# VSCard_v4.net
KiCad netlist of a schematic drawn in EAGLE
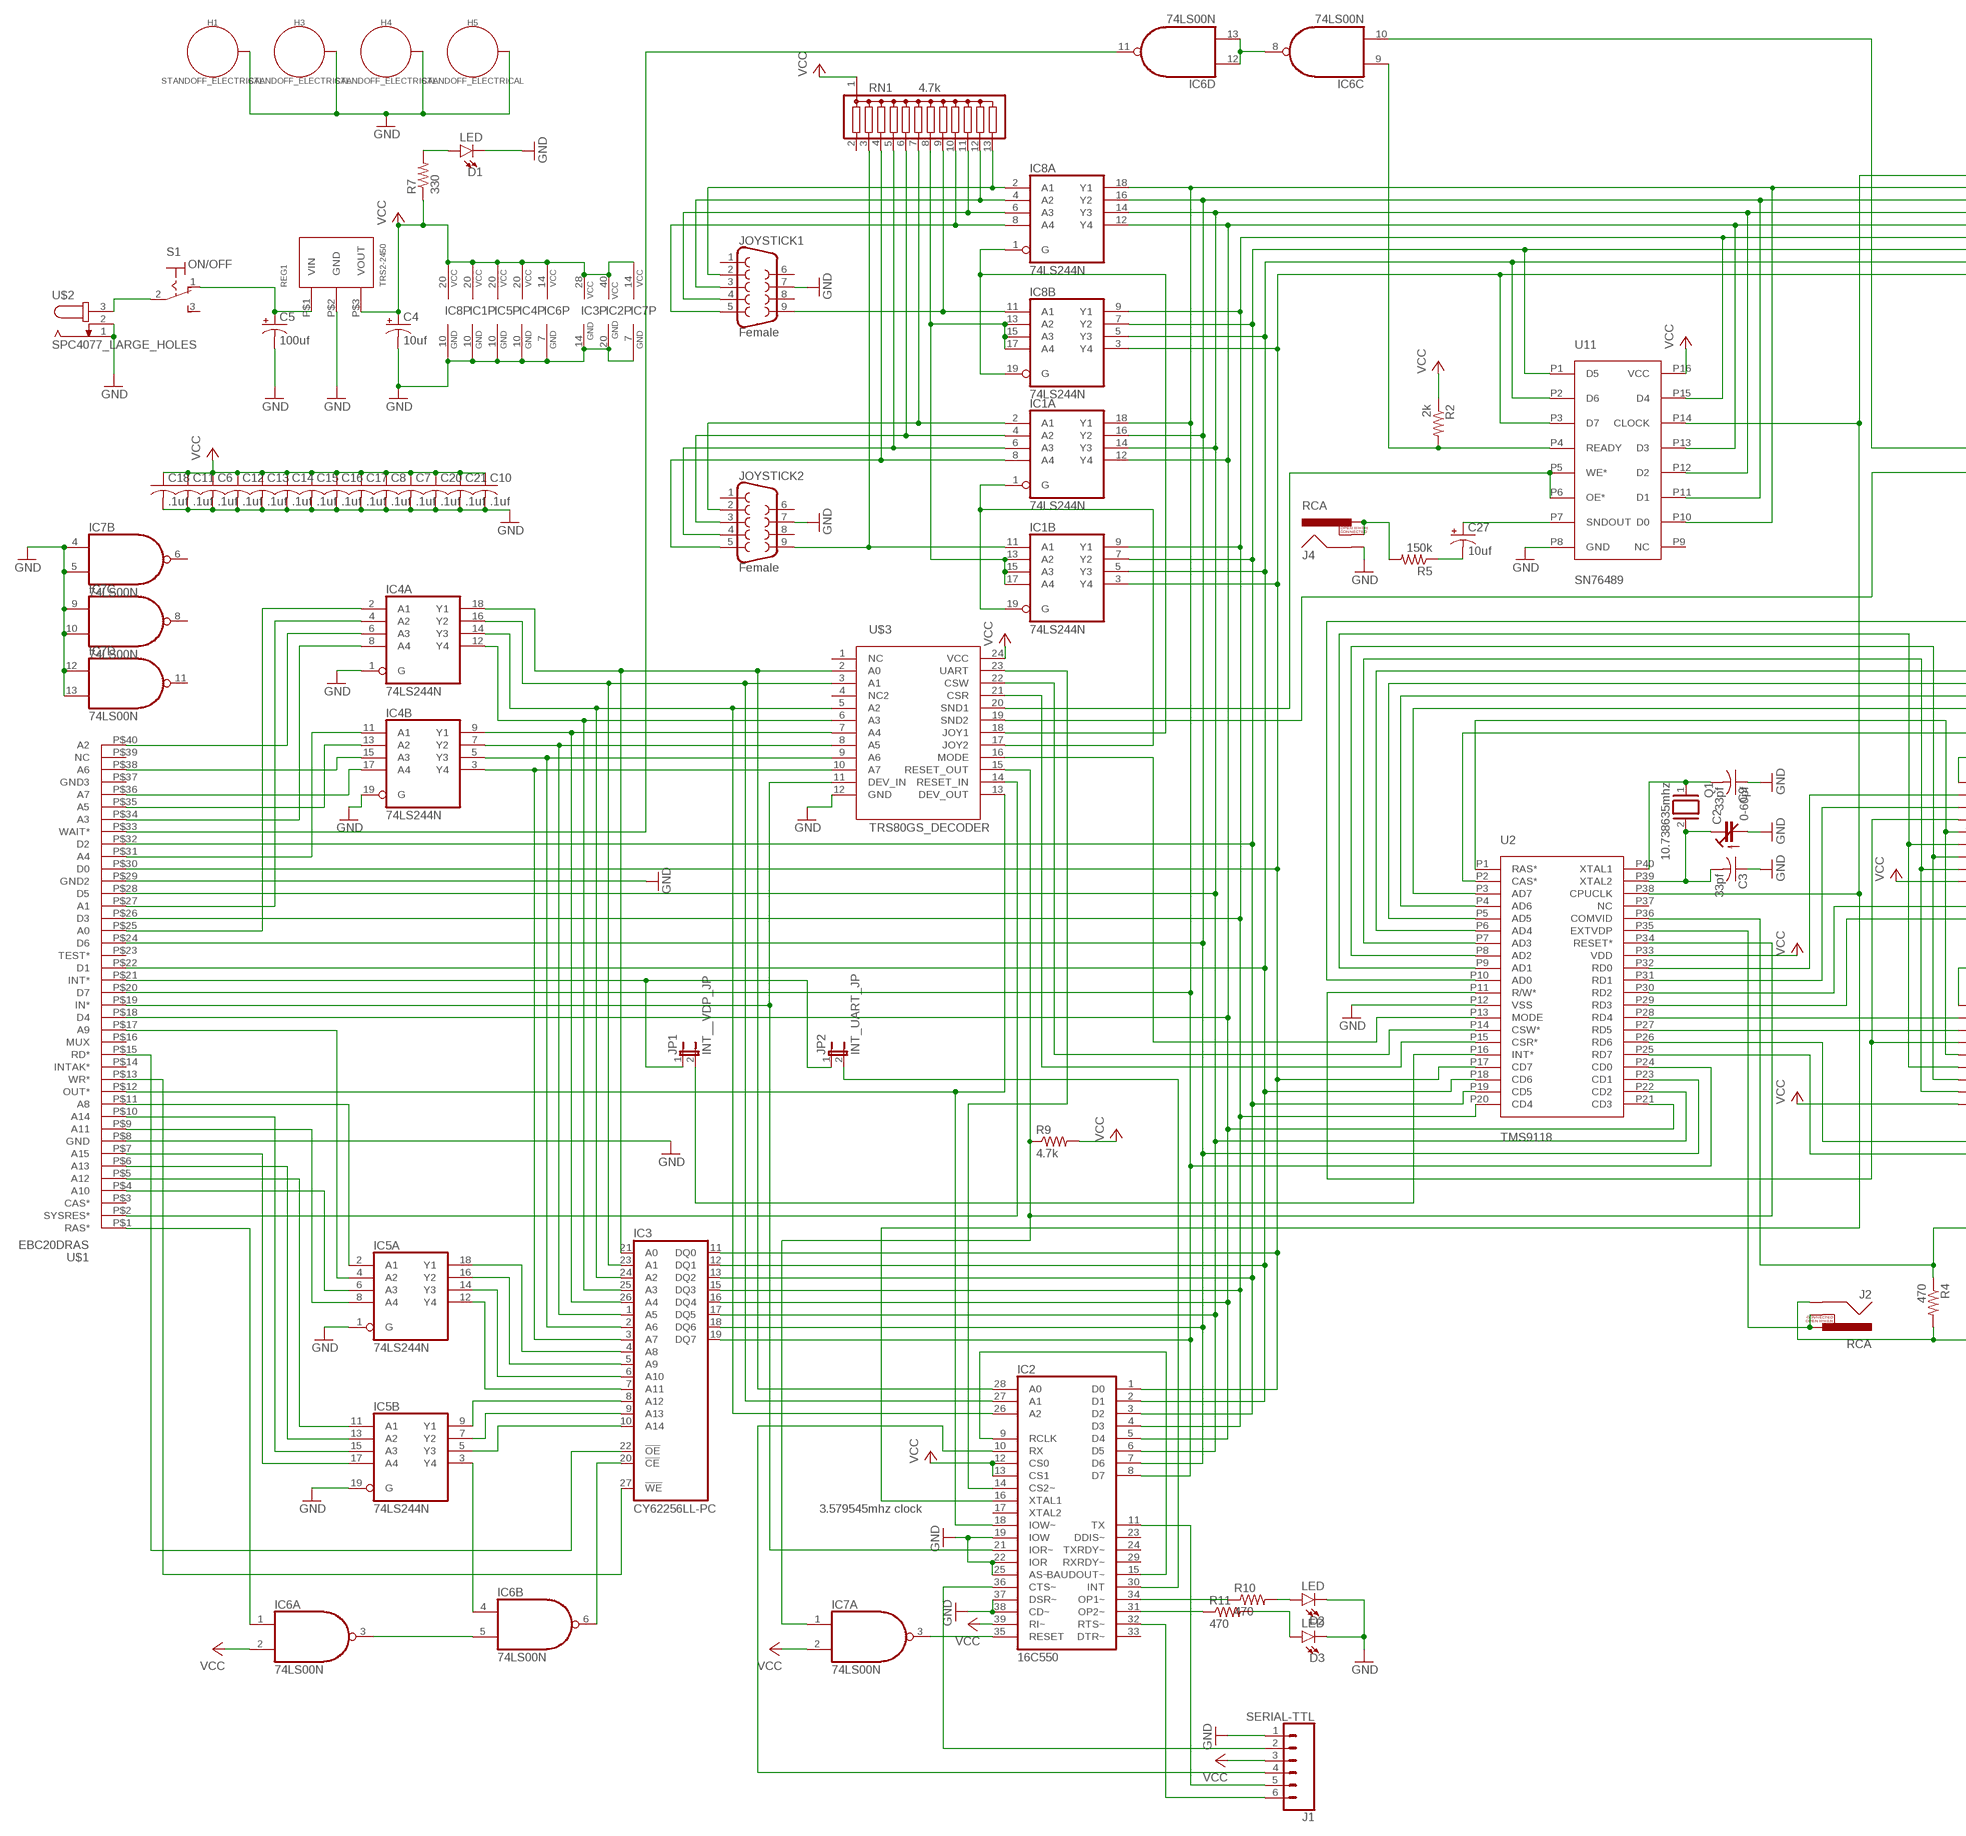
[diagram p0: schematic, sheet 1, part 1 of 2]
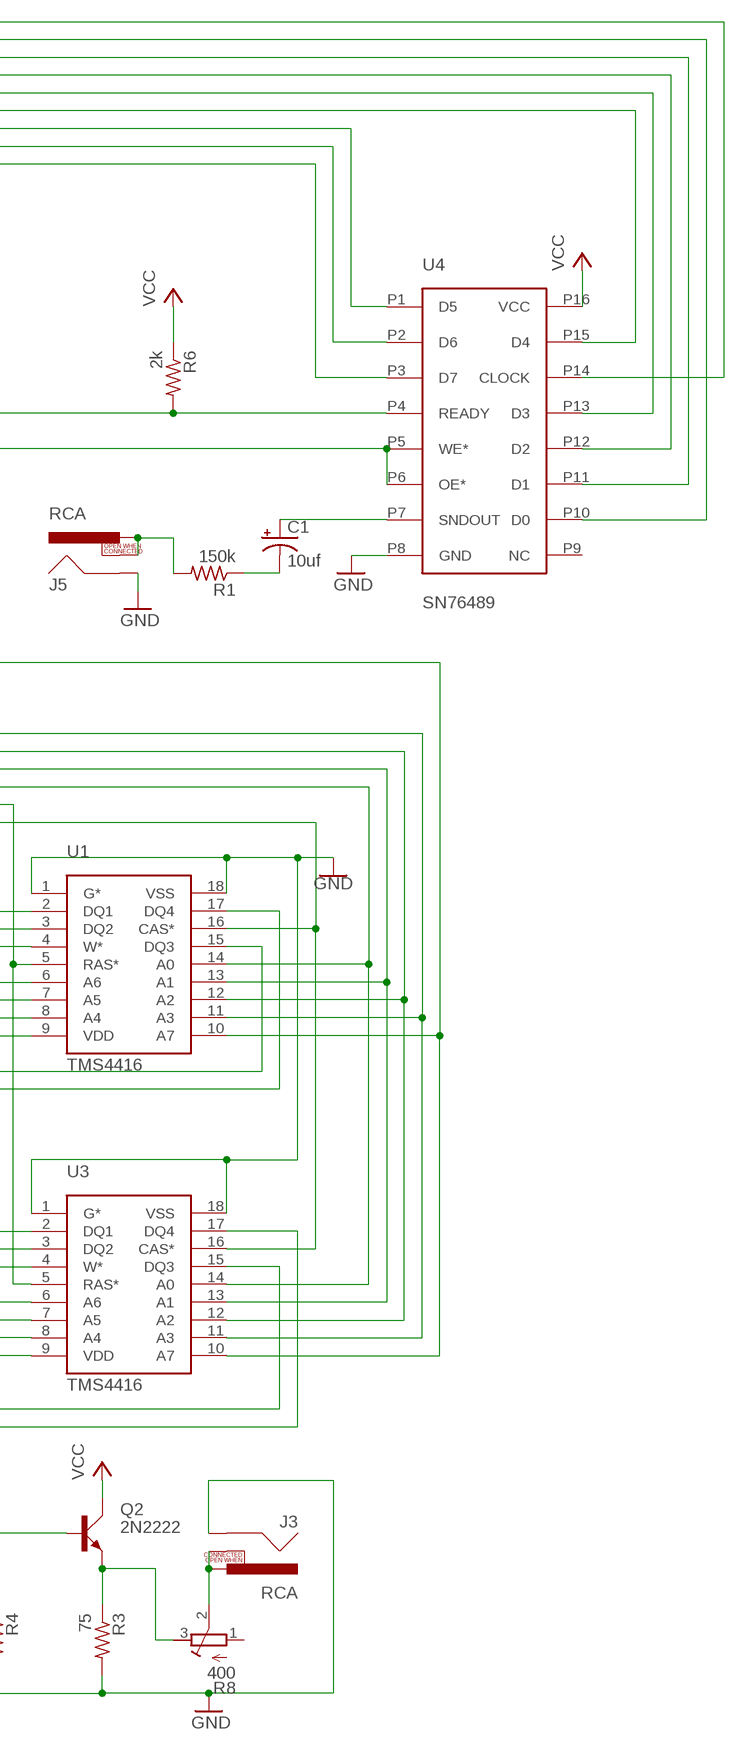
[diagram p1: schematic, sheet 1, part 2 of 2]

(export (version "E")
  (design (tool "Eeschema 10.0.6"))
  (components
    (comp (ref "C1")
      (value "10uf")
      (footprint "eagle-import:E2,5-6")
      (libsource (lib "eagle-import") (part "resistor_348_CPOL-USE2.5-6"))
    )
    (comp (ref "C2")
      (value "0-60pf")
      (footprint "eagle-import:CTRIM3050.504")
      (libsource (lib "eagle-import") (part "C-TRIMM3050.504"))
    )
    (comp (ref "C3")
      (value "33pf")
      (footprint "eagle-import:C050-050X075")
      (libsource (lib "eagle-import") (part "C-US050-050X075"))
    )
    (comp (ref "C4")
      (value "10uf")
      (footprint "eagle-import:E2,5-5")
      (libsource (lib "eagle-import") (part "resistor_348_CPOL-USE2.5-5"))
    )
    (comp (ref "C5")
      (value "100uf")
      (footprint "eagle-import:E3,5-10")
      (libsource (lib "eagle-import") (part "CPOL-USE3.5-10"))
    )
    (comp (ref "C6")
      (value ".1uf")
      (footprint "eagle-import:C025-025X050")
      (libsource (lib "eagle-import") (part "resistor_348_C-US025-025X050"))
    )
    (comp (ref "C7")
      (value ".1uf")
      (footprint "eagle-import:C025-025X050")
      (libsource (lib "eagle-import") (part "resistor_348_C-US025-025X050"))
    )
    (comp (ref "C8")
      (value ".1uf")
      (footprint "eagle-import:C025-025X050")
      (libsource (lib "eagle-import") (part "resistor_348_C-US025-025X050"))
    )
    (comp (ref "C9")
      (value "33pf")
      (footprint "eagle-import:C050-050X075")
      (libsource (lib "eagle-import") (part "C-US050-050X075"))
    )
    (comp (ref "C10")
      (value ".1uf")
      (footprint "eagle-import:C025-025X050")
      (libsource (lib "eagle-import") (part "resistor_348_C-US025-025X050"))
    )
    (comp (ref "C11")
      (value ".1uf")
      (footprint "eagle-import:C025-025X050")
      (libsource (lib "eagle-import") (part "resistor_348_C-US025-025X050"))
    )
    (comp (ref "C12")
      (value ".1uf")
      (footprint "eagle-import:C025-025X050")
      (libsource (lib "eagle-import") (part "resistor_348_C-US025-025X050"))
    )
    (comp (ref "C13")
      (value ".1uf")
      (footprint "eagle-import:C025-025X050")
      (libsource (lib "eagle-import") (part "resistor_348_C-US025-025X050"))
    )
    (comp (ref "C14")
      (value ".1uf")
      (footprint "eagle-import:C025-025X050")
      (libsource (lib "eagle-import") (part "resistor_348_C-US025-025X050"))
    )
    (comp (ref "C15")
      (value ".1uf")
      (footprint "eagle-import:C025-025X050")
      (libsource (lib "eagle-import") (part "resistor_348_C-US025-025X050"))
    )
    (comp (ref "C16")
      (value ".1uf")
      (footprint "eagle-import:C025-025X050")
      (libsource (lib "eagle-import") (part "resistor_348_C-US025-025X050"))
    )
    (comp (ref "C17")
      (value ".1uf")
      (footprint "eagle-import:C025-025X050")
      (libsource (lib "eagle-import") (part "resistor_348_C-US025-025X050"))
    )
    (comp (ref "C18")
      (value ".1uf")
      (footprint "eagle-import:C025-025X050")
      (libsource (lib "eagle-import") (part "resistor_348_C-US025-025X050"))
    )
    (comp (ref "C20")
      (value ".1uf")
      (footprint "eagle-import:C025-025X050")
      (libsource (lib "eagle-import") (part "resistor_348_C-US025-025X050"))
    )
    (comp (ref "C21")
      (value ".1uf")
      (footprint "eagle-import:C025-025X050")
      (libsource (lib "eagle-import") (part "resistor_348_C-US025-025X050"))
    )
    (comp (ref "C27")
      (value "10uf")
      (footprint "eagle-import:E2,5-6")
      (libsource (lib "eagle-import") (part "resistor_348_CPOL-USE2.5-6"))
    )
    (comp (ref "D1")
      (value "LED")
      (footprint "eagle-import:LED_3MM")
      (libsource (lib "eagle-import") (part "LED3MM"))
    )
    (comp (ref "D2")
      (value "LED")
      (footprint "eagle-import:LED_3MM")
      (libsource (lib "eagle-import") (part "LED3MM"))
    )
    (comp (ref "D3")
      (value "LED")
      (footprint "eagle-import:LED_3MM")
      (libsource (lib "eagle-import") (part "LED3MM"))
    )
    (comp (ref "H1")
      (value "STANDOFF_ELECTRICAL")
      (footprint "eagle-import:STANDOFF-ELECTRICAL")
      (libsource (lib "eagle-import") (part "STANDOFF_ELECTRICAL"))
    )
    (comp (ref "H3")
      (value "STANDOFF_ELECTRICAL")
      (footprint "eagle-import:STANDOFF-ELECTRICAL")
      (libsource (lib "eagle-import") (part "STANDOFF_ELECTRICAL"))
    )
    (comp (ref "H4")
      (value "STANDOFF_ELECTRICAL")
      (footprint "eagle-import:STANDOFF-ELECTRICAL")
      (libsource (lib "eagle-import") (part "STANDOFF_ELECTRICAL"))
    )
    (comp (ref "H5")
      (value "STANDOFF_ELECTRICAL")
      (footprint "eagle-import:STANDOFF-ELECTRICAL")
      (libsource (lib "eagle-import") (part "STANDOFF_ELECTRICAL"))
    )
    (comp (ref "IC1")
      (value "74LS244N")
      (footprint "eagle-import:DIL20")
      (libsource (lib "eagle-import") (part "74244NLS"))
    )
    (comp (ref "IC2")
      (value "16C550")
      (footprint "eagle-import:DIL40")
      (fields (field (name "MPN") "ST16C450CP40"))
      (libsource (lib "eagle-import") (part "XR-16C550P"))
    )
    (comp (ref "IC3")
      (value "CY62256LL-PC")
      (footprint "eagle-import:DIL28-6")
      (libsource (lib "eagle-import") (part "CY62256LL-?PC"))
    )
    (comp (ref "IC4")
      (value "74LS244N")
      (footprint "eagle-import:DIL20")
      (libsource (lib "eagle-import") (part "74244NLS"))
    )
    (comp (ref "IC5")
      (value "74LS244N")
      (footprint "eagle-import:DIL20")
      (libsource (lib "eagle-import") (part "74244NLS"))
    )
    (comp (ref "IC6")
      (value "74LS00N")
      (footprint "eagle-import:DIL14")
      (libsource (lib "eagle-import") (part "7400NLS"))
    )
    (comp (ref "IC7")
      (value "74LS00N")
      (footprint "eagle-import:DIL14")
      (libsource (lib "eagle-import") (part "7400NLS"))
    )
    (comp (ref "IC8")
      (value "74LS244N")
      (footprint "eagle-import:DIL20")
      (libsource (lib "eagle-import") (part "74244NLS"))
    )
    (comp (ref "J1")
      (value "SERIAL-TTL")
      (footprint "eagle-import:1X06_NO_SILK")
      (libsource (lib "eagle-import") (part "CONN_06NO_SILK_FEMALE_PTH"))
    )
    (comp (ref "J2")
      (value "RCA")
      (footprint "eagle-import:RCA")
      (libsource (lib "eagle-import") (part "RCA"))
    )
    (comp (ref "J3")
      (value "RCA")
      (footprint "eagle-import:RCA")
      (libsource (lib "eagle-import") (part "RCA"))
    )
    (comp (ref "J4")
      (value "RCA")
      (footprint "eagle-import:RCA")
      (libsource (lib "eagle-import") (part "RCA"))
    )
    (comp (ref "J5")
      (value "RCA")
      (footprint "eagle-import:RCA")
      (libsource (lib "eagle-import") (part "RCA"))
    )
    (comp (ref "JOYSTICK1")
      (value "Female")
      (footprint "eagle-import:DB9")
      (libsource (lib "eagle-import") (part "DB9FEMALE"))
    )
    (comp (ref "JOYSTICK2")
      (value "Female")
      (footprint "eagle-import:DB9")
      (libsource (lib "eagle-import") (part "DB9FEMALE"))
    )
    (comp (ref "JP1")
      (value "INT__VDP_JP")
      (footprint "eagle-import:JP1")
      (libsource (lib "eagle-import") (part "JP1E"))
    )
    (comp (ref "JP2")
      (value "INT_UART_JP")
      (footprint "eagle-import:JP1")
      (libsource (lib "eagle-import") (part "JP1E"))
    )
    (comp (ref "Q1")
      (value "10.738635mhz")
      (footprint "eagle-import:QS")
      (libsource (lib "eagle-import") (part "XTAL/S"))
    )
    (comp (ref "Q2")
      (value "2N2222")
      (footprint "eagle-import:TO18A")
      (libsource (lib "eagle-import") (part "2N2222"))
    )
    (comp (ref "R1")
      (value "150k")
      (footprint "eagle-import:0207_2V")
      (libsource (lib "eagle-import") (part "R-US_0207/2V"))
    )
    (comp (ref "R2")
      (value "2k")
      (footprint "eagle-import:0207_2V")
      (libsource (lib "eagle-import") (part "R-US_0207/2V"))
    )
    (comp (ref "R3")
      (value "75")
      (footprint "eagle-import:0207_2V")
      (libsource (lib "eagle-import") (part "R-US_0207/2V"))
    )
    (comp (ref "R4")
      (value "470")
      (footprint "eagle-import:0207_2V")
      (libsource (lib "eagle-import") (part "R-US_0207/2V"))
    )
    (comp (ref "R5")
      (value "150k")
      (footprint "eagle-import:0207_2V")
      (libsource (lib "eagle-import") (part "R-US_0207/2V"))
    )
    (comp (ref "R6")
      (value "2k")
      (footprint "eagle-import:0207_2V")
      (libsource (lib "eagle-import") (part "R-US_0207/2V"))
    )
    (comp (ref "R7")
      (value "330")
      (footprint "eagle-import:0309V")
      (libsource (lib "eagle-import") (part "R-US_0309/V"))
    )
    (comp (ref "R8")
      (value "400")
      (footprint "eagle-import:RTRIM64W")
      (libsource (lib "eagle-import") (part "R-TRIMM64W"))
    )
    (comp (ref "R9")
      (value "4.7k")
      (footprint "eagle-import:0207_2V")
      (libsource (lib "eagle-import") (part "R-US_0207/2V"))
    )
    (comp (ref "R10")
      (value "470")
      (footprint "eagle-import:0207_2V")
      (libsource (lib "eagle-import") (part "R-US_0207/2V"))
    )
    (comp (ref "R11")
      (value "470")
      (footprint "eagle-import:0207_2V")
      (libsource (lib "eagle-import") (part "R-US_0207/2V"))
    )
    (comp (ref "REG1")
      (value "TRS2-2450")
      (footprint "eagle-import:TRACON_REG")
      (libsource (lib "eagle-import") (part "TRS2-2450"))
    )
    (comp (ref "RN1")
      (value "4.7k")
      (footprint "eagle-import:SIL13")
      (libsource (lib "eagle-import") (part "G12R"))
    )
    (comp (ref "S1")
      (value "ON/OFF")
      (footprint "eagle-import:320-916")
      (libsource (lib "eagle-import") (part "320-916"))
    )
    (comp (ref "U$1")
      (value "EBC20DRAS")
      (footprint "eagle-import:EBC20DRAS")
      (libsource (lib "eagle-import") (part "EBC20DRAS"))
    )
    (comp (ref "U$2")
      (value "SPC4077_LARGE_HOLES")
      (footprint "eagle-import:SPC4077")
      (libsource (lib "eagle-import") (part "SPC4077_LARGE_HOLES"))
    )
    (comp (ref "U$3")
      (value "TRS80GS_DECODER")
      (footprint "eagle-import:DIP24SKI")
      (libsource (lib "eagle-import") (part "TRS80GS_DECODER"))
    )
    (comp (ref "U1")
      (value "TMS4416")
      (footprint "eagle-import:DIP18")
      (libsource (lib "eagle-import") (part "TMS4416"))
    )
    (comp (ref "U2")
      (value "TMS9118")
      (footprint "eagle-import:DIP40_MCU")
      (libsource (lib "eagle-import") (part "TMS9118"))
    )
    (comp (ref "U3")
      (value "TMS4416")
      (footprint "eagle-import:DIP18")
      (libsource (lib "eagle-import") (part "TMS4416"))
    )
    (comp (ref "U4")
      (value "SN76489")
      (footprint "eagle-import:DIP16")
      (libsource (lib "eagle-import") (part "SN76489"))
    )
    (comp (ref "U11")
      (value "SN76489")
      (footprint "eagle-import:DIP16")
      (libsource (lib "eagle-import") (part "SN76489"))
    )
  )
  (nets
    (net (code "1") (name "GND") (class "Default")
      (node (ref "C10") (pin "2") (pinfunction "2_2") (pintype "passive"))
      (node (ref "C11") (pin "2") (pinfunction "2_2") (pintype "passive"))
      (node (ref "C12") (pin "2") (pinfunction "2_2") (pintype "passive"))
      (node (ref "C13") (pin "2") (pinfunction "2_2") (pintype "passive"))
      (node (ref "C14") (pin "2") (pinfunction "2_2") (pintype "passive"))
      (node (ref "C15") (pin "2") (pinfunction "2_2") (pintype "passive"))
      (node (ref "C16") (pin "2") (pinfunction "2_2") (pintype "passive"))
      (node (ref "C17") (pin "2") (pinfunction "2_2") (pintype "passive"))
      (node (ref "C18") (pin "2") (pinfunction "2_2") (pintype "passive"))
      (node (ref "C2") (pin "2") (pinfunction "A_2") (pintype "passive"))
      (node (ref "C20") (pin "2") (pinfunction "2_2") (pintype "passive"))
      (node (ref "C21") (pin "2") (pinfunction "2_2") (pintype "passive"))
      (node (ref "C3") (pin "1") (pinfunction "1_1") (pintype "passive"))
      (node (ref "C4") (pin "-") (pinfunction "-_-") (pintype "passive"))
      (node (ref "C5") (pin "-") (pinfunction "-_-") (pintype "passive"))
      (node (ref "C6") (pin "2") (pinfunction "2_2") (pintype "passive"))
      (node (ref "C7") (pin "2") (pinfunction "2_2") (pintype "passive"))
      (node (ref "C8") (pin "2") (pinfunction "2_2") (pintype "passive"))
      (node (ref "C9") (pin "1") (pinfunction "1_1") (pintype "passive"))
      (node (ref "D1") (pin "K") (pinfunction "C_K") (pintype "passive"))
      (node (ref "D2") (pin "K") (pinfunction "C_K") (pintype "passive"))
      (node (ref "D3") (pin "K") (pinfunction "C_K") (pintype "passive"))
      (node (ref "H1") (pin "P1") (pinfunction "P$1_P1") (pintype "bidirectional"))
      (node (ref "H3") (pin "P1") (pinfunction "P$1_P1") (pintype "bidirectional"))
      (node (ref "H4") (pin "P1") (pinfunction "P$1_P1") (pintype "bidirectional"))
      (node (ref "H5") (pin "P1") (pinfunction "P$1_P1") (pintype "bidirectional"))
      (node (ref "IC1") (pin "10") (pinfunction "GND_10") (pintype "power_in"))
      (node (ref "IC2") (pin "19") (pinfunction "IOW_19") (pintype "input"))
      (node (ref "IC2") (pin "20") (pinfunction "GND_20") (pintype "power_in"))
      (node (ref "IC2") (pin "22") (pinfunction "IOR_22") (pintype "input"))
      (node (ref "IC2") (pin "25") (pinfunction "AS~{}_25") (pintype "input"))
      (node (ref "IC2") (pin "37") (pinfunction "DSR~{}_37") (pintype "input"))
      (node (ref "IC2") (pin "38") (pinfunction "CD~{}_38") (pintype "input"))
      (node (ref "IC3") (pin "14") (pinfunction "GND_14") (pintype "power_in"))
      (node (ref "IC4") (pin "1") (pinfunction "G_1") (pintype "input"))
      (node (ref "IC4") (pin "10") (pinfunction "GND_10") (pintype "power_in"))
      (node (ref "IC4") (pin "19") (pinfunction "G_19") (pintype "input"))
      (node (ref "IC5") (pin "1") (pinfunction "G_1") (pintype "input"))
      (node (ref "IC5") (pin "10") (pinfunction "GND_10") (pintype "power_in"))
      (node (ref "IC5") (pin "19") (pinfunction "G_19") (pintype "input"))
      (node (ref "IC6") (pin "7") (pinfunction "GND_7") (pintype "power_in"))
      (node (ref "IC7") (pin "10") (pinfunction "I1_10") (pintype "input"))
      (node (ref "IC7") (pin "12") (pinfunction "I0_12") (pintype "input"))
      (node (ref "IC7") (pin "13") (pinfunction "I1_13") (pintype "input"))
      (node (ref "IC7") (pin "4") (pinfunction "I0_4") (pintype "input"))
      (node (ref "IC7") (pin "5") (pinfunction "I1_5") (pintype "input"))
      (node (ref "IC7") (pin "7") (pinfunction "GND_7") (pintype "power_in"))
      (node (ref "IC7") (pin "9") (pinfunction "I0_9") (pintype "input"))
      (node (ref "IC8") (pin "10") (pinfunction "GND_10") (pintype "power_in"))
      (node (ref "J1") (pin "1") (pinfunction "1_1") (pintype "passive"))
      (node (ref "J2") (pin "SHELL") (pinfunction "SHELL_SHELL") (pintype "bidirectional"))
      (node (ref "J3") (pin "SHELL") (pinfunction "SHELL_SHELL") (pintype "bidirectional"))
      (node (ref "J4") (pin "SHELL") (pinfunction "SHELL_SHELL") (pintype "bidirectional"))
      (node (ref "J5") (pin "SHELL") (pinfunction "SHELL_SHELL") (pintype "bidirectional"))
      (node (ref "JOYSTICK1") (pin "7") (pinfunction "7_7") (pintype "passive"))
      (node (ref "JOYSTICK2") (pin "7") (pinfunction "7_7") (pintype "passive"))
      (node (ref "R3") (pin "2") (pinfunction "2_2") (pintype "passive"))
      (node (ref "R4") (pin "2") (pinfunction "2_2") (pintype "passive"))
      (node (ref "REG1") (pin "P$2") (pinfunction "GND_P$2") (pintype "bidirectional"))
      (node (ref "U$1") (pin "P$29") (pinfunction "GND2_P$29") (pintype "bidirectional"))
      (node (ref "U$1") (pin "P$8") (pinfunction "GND_P$8") (pintype "bidirectional"))
      (node (ref "U$2") (pin "1") (pinfunction "1_1") (pintype "passive"))
      (node (ref "U$2") (pin "2") (pinfunction "2_2") (pintype "passive"))
      (node (ref "U$3") (pin "12") (pinfunction "GND_12") (pintype "bidirectional"))
      (node (ref "U1") (pin "1") (pinfunction "G*_1") (pintype "bidirectional"))
      (node (ref "U1") (pin "18") (pinfunction "VSS_18") (pintype "bidirectional"))
      (node (ref "U11") (pin "P8") (pinfunction "GND_P8") (pintype "bidirectional"))
      (node (ref "U2") (pin "P12") (pinfunction "VSS_P12") (pintype "bidirectional"))
      (node (ref "U3") (pin "1") (pinfunction "G*_1") (pintype "bidirectional"))
      (node (ref "U3") (pin "18") (pinfunction "VSS_18") (pintype "bidirectional"))
      (node (ref "U4") (pin "P8") (pinfunction "GND_P8") (pintype "bidirectional"))
    )
    (net (code "2") (name "Net-(C1-Pad-)") (class "Default")
      (node (ref "C1") (pin "-") (pinfunction "-_-") (pintype "passive"))
      (node (ref "R1") (pin "1") (pinfunction "1_1") (pintype "passive"))
    )
    (net (code "3") (name "Net-(C2-E)") (class "Default")
      (node (ref "C2") (pin "1") (pinfunction "E_1") (pintype "passive"))
      (node (ref "C3") (pin "2") (pinfunction "2_2") (pintype "passive"))
      (node (ref "Q1") (pin "2") (pinfunction "2_2") (pintype "passive"))
      (node (ref "U2") (pin "P39") (pinfunction "XTAL2_P39") (pintype "bidirectional"))
    )
    (net (code "4") (name "Net-(C27-Pad-)") (class "Default")
      (node (ref "C27") (pin "-") (pinfunction "-_-") (pintype "passive"))
      (node (ref "R5") (pin "1") (pinfunction "1_1") (pintype "passive"))
    )
    (net (code "5") (name "Net-(D1-PadA)") (class "Default")
      (node (ref "D1") (pin "A") (pinfunction "A_A") (pintype "passive"))
      (node (ref "R7") (pin "2") (pinfunction "2_2") (pintype "passive"))
    )
    (net (code "6") (name "Net-(D2-PadA)") (class "Default")
      (node (ref "D2") (pin "A") (pinfunction "A_A") (pintype "passive"))
      (node (ref "R10") (pin "2") (pinfunction "2_2") (pintype "passive"))
    )
    (net (code "7") (name "Net-(D3-PadA)") (class "Default")
      (node (ref "D3") (pin "A") (pinfunction "A_A") (pintype "passive"))
      (node (ref "R11") (pin "2") (pinfunction "2_2") (pintype "passive"))
    )
    (net (code "8") (name "Net-(IC1A-A1)") (class "Default")
      (node (ref "IC1") (pin "2") (pinfunction "A1_2") (pintype "input"))
      (node (ref "JOYSTICK2") (pin "2") (pinfunction "2_2") (pintype "passive"))
      (node (ref "RN1") (pin "7") (pinfunction "7_7") (pintype "passive"))
    )
    (net (code "9") (name "Net-(IC1A-A2)") (class "Default")
      (node (ref "IC1") (pin "4") (pinfunction "A2_4") (pintype "input"))
      (node (ref "JOYSTICK2") (pin "3") (pinfunction "3_3") (pintype "passive"))
      (node (ref "RN1") (pin "6") (pinfunction "6_6") (pintype "passive"))
    )
    (net (code "10") (name "Net-(IC1A-A3)") (class "Default")
      (node (ref "IC1") (pin "6") (pinfunction "A3_6") (pintype "input"))
      (node (ref "JOYSTICK2") (pin "4") (pinfunction "4_4") (pintype "passive"))
      (node (ref "RN1") (pin "5") (pinfunction "5_5") (pintype "passive"))
    )
    (net (code "11") (name "Net-(IC1A-A4)") (class "Default")
      (node (ref "IC1") (pin "8") (pinfunction "A4_8") (pintype "input"))
      (node (ref "JOYSTICK2") (pin "5") (pinfunction "5_5") (pintype "passive"))
      (node (ref "RN1") (pin "4") (pinfunction "4_4") (pintype "passive"))
    )
    (net (code "12") (name "Net-(IC1A-G)") (class "Default")
      (node (ref "IC1") (pin "1") (pinfunction "G_1") (pintype "input"))
      (node (ref "IC1") (pin "19") (pinfunction "G_19") (pintype "input"))
      (node (ref "U$3") (pin "17") (pinfunction "JOY2_17") (pintype "bidirectional"))
    )
    (net (code "13") (name "Net-(IC1A-Y1)") (class "Default")
      (node (ref "IC1") (pin "18") (pinfunction "Y1_18") (pintype "tri_state"))
      (node (ref "IC2") (pin "8") (pinfunction "D7_8") (pintype "bidirectional"))
      (node (ref "IC3") (pin "19") (pinfunction "DQ7_19") (pintype "bidirectional"))
      (node (ref "IC8") (pin "18") (pinfunction "Y1_18") (pintype "tri_state"))
      (node (ref "U$1") (pin "P$20") (pinfunction "D7_P$20") (pintype "bidirectional"))
      (node (ref "U11") (pin "P10") (pinfunction "D0_P10") (pintype "bidirectional"))
      (node (ref "U2") (pin "P24") (pinfunction "CD0_P24") (pintype "bidirectional"))
      (node (ref "U4") (pin "P10") (pinfunction "D0_P10") (pintype "bidirectional"))
    )
    (net (code "14") (name "Net-(IC1A-Y2)") (class "Default")
      (node (ref "IC1") (pin "16") (pinfunction "Y2_16") (pintype "tri_state"))
      (node (ref "IC2") (pin "7") (pinfunction "D6_7") (pintype "bidirectional"))
      (node (ref "IC3") (pin "18") (pinfunction "DQ6_18") (pintype "bidirectional"))
      (node (ref "IC8") (pin "16") (pinfunction "Y2_16") (pintype "tri_state"))
      (node (ref "U$1") (pin "P$24") (pinfunction "D6_P$24") (pintype "bidirectional"))
      (node (ref "U11") (pin "P11") (pinfunction "D1_P11") (pintype "bidirectional"))
      (node (ref "U2") (pin "P23") (pinfunction "CD1_P23") (pintype "bidirectional"))
      (node (ref "U4") (pin "P11") (pinfunction "D1_P11") (pintype "bidirectional"))
    )
    (net (code "15") (name "Net-(IC1A-Y3)") (class "Default")
      (node (ref "IC1") (pin "14") (pinfunction "Y3_14") (pintype "tri_state"))
      (node (ref "IC2") (pin "6") (pinfunction "D5_6") (pintype "bidirectional"))
      (node (ref "IC3") (pin "17") (pinfunction "DQ5_17") (pintype "bidirectional"))
      (node (ref "IC8") (pin "14") (pinfunction "Y3_14") (pintype "tri_state"))
      (node (ref "U$1") (pin "P$28") (pinfunction "D5_P$28") (pintype "bidirectional"))
      (node (ref "U11") (pin "P12") (pinfunction "D2_P12") (pintype "bidirectional"))
      (node (ref "U2") (pin "P22") (pinfunction "CD2_P22") (pintype "bidirectional"))
      (node (ref "U4") (pin "P12") (pinfunction "D2_P12") (pintype "bidirectional"))
    )
    (net (code "16") (name "Net-(IC1A-Y4)") (class "Default")
      (node (ref "IC1") (pin "12") (pinfunction "Y4_12") (pintype "tri_state"))
      (node (ref "IC2") (pin "5") (pinfunction "D4_5") (pintype "bidirectional"))
      (node (ref "IC3") (pin "16") (pinfunction "DQ4_16") (pintype "bidirectional"))
      (node (ref "IC8") (pin "12") (pinfunction "Y4_12") (pintype "tri_state"))
      (node (ref "U$1") (pin "P$18") (pinfunction "D4_P$18") (pintype "bidirectional"))
      (node (ref "U11") (pin "P13") (pinfunction "D3_P13") (pintype "bidirectional"))
      (node (ref "U2") (pin "P21") (pinfunction "CD3_P21") (pintype "bidirectional"))
      (node (ref "U4") (pin "P13") (pinfunction "D3_P13") (pintype "bidirectional"))
    )
    (net (code "17") (name "Net-(IC1B-A1)") (class "Default")
      (node (ref "IC1") (pin "11") (pinfunction "A1_11") (pintype "input"))
      (node (ref "JOYSTICK2") (pin "9") (pinfunction "9_9") (pintype "passive"))
      (node (ref "RN1") (pin "3") (pinfunction "3_3") (pintype "passive"))
    )
    (net (code "18") (name "Net-(IC1B-A2)") (class "Default")
      (node (ref "IC1") (pin "13") (pinfunction "A2_13") (pintype "input"))
      (node (ref "IC1") (pin "15") (pinfunction "A3_15") (pintype "input"))
      (node (ref "IC1") (pin "17") (pinfunction "A4_17") (pintype "input"))
      (node (ref "IC8") (pin "13") (pinfunction "A2_13") (pintype "input"))
      (node (ref "IC8") (pin "15") (pinfunction "A3_15") (pintype "input"))
      (node (ref "IC8") (pin "17") (pinfunction "A4_17") (pintype "input"))
      (node (ref "RN1") (pin "8") (pinfunction "8_8") (pintype "passive"))
    )
    (net (code "19") (name "Net-(IC1B-Y1)") (class "Default")
      (node (ref "IC1") (pin "9") (pinfunction "Y1_9") (pintype "tri_state"))
      (node (ref "IC2") (pin "4") (pinfunction "D3_4") (pintype "bidirectional"))
      (node (ref "IC3") (pin "15") (pinfunction "DQ3_15") (pintype "bidirectional"))
      (node (ref "IC8") (pin "9") (pinfunction "Y1_9") (pintype "tri_state"))
      (node (ref "U$1") (pin "P$26") (pinfunction "D3_P$26") (pintype "bidirectional"))
      (node (ref "U11") (pin "P15") (pinfunction "D4_P15") (pintype "bidirectional"))
      (node (ref "U2") (pin "P20") (pinfunction "CD4_P20") (pintype "bidirectional"))
      (node (ref "U4") (pin "P15") (pinfunction "D4_P15") (pintype "bidirectional"))
    )
    (net (code "20") (name "Net-(IC1B-Y2)") (class "Default")
      (node (ref "IC1") (pin "7") (pinfunction "Y2_7") (pintype "tri_state"))
      (node (ref "IC2") (pin "3") (pinfunction "D2_3") (pintype "bidirectional"))
      (node (ref "IC3") (pin "13") (pinfunction "DQ2_13") (pintype "bidirectional"))
      (node (ref "IC8") (pin "7") (pinfunction "Y2_7") (pintype "tri_state"))
      (node (ref "U$1") (pin "P$32") (pinfunction "D2_P$32") (pintype "bidirectional"))
      (node (ref "U11") (pin "P1") (pinfunction "D5_P1") (pintype "bidirectional"))
      (node (ref "U2") (pin "P19") (pinfunction "CD5_P19") (pintype "bidirectional"))
      (node (ref "U4") (pin "P1") (pinfunction "D5_P1") (pintype "bidirectional"))
    )
    (net (code "21") (name "Net-(IC1B-Y3)") (class "Default")
      (node (ref "IC1") (pin "5") (pinfunction "Y3_5") (pintype "tri_state"))
      (node (ref "IC2") (pin "2") (pinfunction "D1_2") (pintype "bidirectional"))
      (node (ref "IC3") (pin "12") (pinfunction "DQ1_12") (pintype "bidirectional"))
      (node (ref "IC8") (pin "5") (pinfunction "Y3_5") (pintype "tri_state"))
      (node (ref "U$1") (pin "P$22") (pinfunction "D1_P$22") (pintype "bidirectional"))
      (node (ref "U11") (pin "P2") (pinfunction "D6_P2") (pintype "bidirectional"))
      (node (ref "U2") (pin "P18") (pinfunction "CD6_P18") (pintype "bidirectional"))
      (node (ref "U4") (pin "P2") (pinfunction "D6_P2") (pintype "bidirectional"))
    )
    (net (code "22") (name "Net-(IC1B-Y4)") (class "Default")
      (node (ref "IC1") (pin "3") (pinfunction "Y4_3") (pintype "tri_state"))
      (node (ref "IC2") (pin "1") (pinfunction "D0_1") (pintype "bidirectional"))
      (node (ref "IC3") (pin "11") (pinfunction "DQ0_11") (pintype "bidirectional"))
      (node (ref "IC8") (pin "3") (pinfunction "Y4_3") (pintype "tri_state"))
      (node (ref "U$1") (pin "P$30") (pinfunction "D0_P$30") (pintype "bidirectional"))
      (node (ref "U11") (pin "P3") (pinfunction "D7_P3") (pintype "bidirectional"))
      (node (ref "U2") (pin "P17") (pinfunction "CD7_P17") (pintype "bidirectional"))
      (node (ref "U4") (pin "P3") (pinfunction "D7_P3") (pintype "bidirectional"))
    )
    (net (code "23") (name "Net-(IC2A-A0)") (class "Default")
      (node (ref "IC2") (pin "28") (pinfunction "A0_28") (pintype "input"))
      (node (ref "IC3") (pin "21") (pinfunction "A0_21") (pintype "input"))
      (node (ref "IC4") (pin "18") (pinfunction "Y1_18") (pintype "tri_state"))
      (node (ref "U$3") (pin "2") (pinfunction "A0_2") (pintype "bidirectional"))
    )
    (net (code "24") (name "Net-(IC2A-A1)") (class "Default")
      (node (ref "IC2") (pin "27") (pinfunction "A1_27") (pintype "input"))
      (node (ref "IC3") (pin "23") (pinfunction "A1_23") (pintype "input"))
      (node (ref "IC4") (pin "16") (pinfunction "Y2_16") (pintype "tri_state"))
      (node (ref "U$3") (pin "3") (pinfunction "A1_3") (pintype "bidirectional"))
    )
    (net (code "25") (name "Net-(IC2A-A2)") (class "Default")
      (node (ref "IC2") (pin "26") (pinfunction "A2_26") (pintype "input"))
      (node (ref "IC3") (pin "24") (pinfunction "A2_24") (pintype "input"))
      (node (ref "IC4") (pin "14") (pinfunction "Y3_14") (pintype "tri_state"))
      (node (ref "U$3") (pin "5") (pinfunction "A2_5") (pintype "bidirectional"))
    )
    (net (code "26") (name "Net-(IC2A-BAUDOUT~{})") (class "Default")
      (node (ref "IC2") (pin "15") (pinfunction "BAUDOUT~{}_15") (pintype "output"))
      (node (ref "IC2") (pin "9") (pinfunction "RCLK_9") (pintype "input"))
    )
    (net (code "27") (name "Net-(IC2A-CS2~{})") (class "Default")
      (node (ref "IC2") (pin "14") (pinfunction "CS2~{}_14") (pintype "input"))
      (node (ref "U$3") (pin "23") (pinfunction "UART_23") (pintype "bidirectional"))
    )
    (net (code "28") (name "Net-(IC2A-CTS~{})") (class "Default")
      (node (ref "IC2") (pin "36") (pinfunction "CTS~{}_36") (pintype "input"))
      (node (ref "J1") (pin "2") (pinfunction "2_2") (pintype "passive"))
    )
    (net (code "29") (name "Net-(IC2A-INT)") (class "Default")
      (node (ref "IC2") (pin "30") (pinfunction "INT_30") (pintype "output"))
      (node (ref "JP2") (pin "2") (pinfunction "2_2") (pintype "passive"))
    )
    (net (code "30") (name "Net-(IC2A-IOR~{})") (class "Default")
      (node (ref "IC2") (pin "21") (pinfunction "IOR~{}_21") (pintype "input"))
      (node (ref "U$1") (pin "P$19") (pinfunction "IN*_P$19") (pintype "bidirectional"))
      (node (ref "U$3") (pin "11") (pinfunction "DEV_IN_11") (pintype "bidirectional"))
    )
    (net (code "31") (name "Net-(IC2A-IOW~{})") (class "Default")
      (node (ref "IC2") (pin "18") (pinfunction "IOW~{}_18") (pintype "input"))
      (node (ref "U$1") (pin "P$12") (pinfunction "OUT*_P$12") (pintype "bidirectional"))
      (node (ref "U$3") (pin "13") (pinfunction "DEV_OUT_13") (pintype "bidirectional"))
    )
    (net (code "32") (name "Net-(IC2A-OP1~{})") (class "Default")
      (node (ref "IC2") (pin "34") (pinfunction "OP1~{}_34") (pintype "output"))
      (node (ref "R10") (pin "1") (pinfunction "1_1") (pintype "passive"))
    )
    (net (code "33") (name "Net-(IC2A-OP2~{})") (class "Default")
      (node (ref "IC2") (pin "31") (pinfunction "OP2~{}_31") (pintype "output"))
      (node (ref "R11") (pin "1") (pinfunction "1_1") (pintype "passive"))
    )
    (net (code "34") (name "Net-(IC2A-RESET)") (class "Default")
      (node (ref "IC2") (pin "35") (pinfunction "RESET_35") (pintype "input"))
      (node (ref "IC7") (pin "3") (pinfunction "O_3") (pintype "output"))
    )
    (net (code "35") (name "Net-(IC2A-RTS~{})") (class "Default")
      (node (ref "IC2") (pin "32") (pinfunction "RTS~{}_32") (pintype "output"))
      (node (ref "J1") (pin "6") (pinfunction "6_6") (pintype "passive"))
    )
    (net (code "36") (name "Net-(IC2A-RX)") (class "Default")
      (node (ref "IC2") (pin "10") (pinfunction "RX_10") (pintype "input"))
      (node (ref "J1") (pin "4") (pinfunction "4_4") (pintype "passive"))
    )
    (net (code "37") (name "Net-(IC2A-TX)") (class "Default")
      (node (ref "IC2") (pin "11") (pinfunction "TX_11") (pintype "output"))
      (node (ref "J1") (pin "5") (pinfunction "5_5") (pintype "passive"))
    )
    (net (code "38") (name "Net-(IC2A-XTAL1)") (class "Default")
      (node (ref "IC2") (pin "16") (pinfunction "XTAL1_16") (pintype "input"))
      (node (ref "U11") (pin "P14") (pinfunction "CLOCK_P14") (pintype "bidirectional"))
      (node (ref "U2") (pin "P38") (pinfunction "CPUCLK_P38") (pintype "bidirectional"))
      (node (ref "U4") (pin "P14") (pinfunction "CLOCK_P14") (pintype "bidirectional"))
    )
    (net (code "39") (name "Net-(IC3A-A3)") (class "Default")
      (node (ref "IC3") (pin "25") (pinfunction "A3_25") (pintype "input"))
      (node (ref "IC4") (pin "12") (pinfunction "Y4_12") (pintype "tri_state"))
      (node (ref "U$3") (pin "6") (pinfunction "A3_6") (pintype "bidirectional"))
    )
    (net (code "40") (name "Net-(IC3A-A4)") (class "Default")
      (node (ref "IC3") (pin "26") (pinfunction "A4_26") (pintype "input"))
      (node (ref "IC4") (pin "9") (pinfunction "Y1_9") (pintype "tri_state"))
      (node (ref "U$3") (pin "7") (pinfunction "A4_7") (pintype "bidirectional"))
    )
    (net (code "41") (name "Net-(IC3A-A5)") (class "Default")
      (node (ref "IC3") (pin "1") (pinfunction "A5_1") (pintype "input"))
      (node (ref "IC4") (pin "7") (pinfunction "Y2_7") (pintype "tri_state"))
      (node (ref "U$3") (pin "8") (pinfunction "A5_8") (pintype "bidirectional"))
    )
    (net (code "42") (name "Net-(IC3A-A6)") (class "Default")
      (node (ref "IC3") (pin "2") (pinfunction "A6_2") (pintype "input"))
      (node (ref "IC4") (pin "5") (pinfunction "Y3_5") (pintype "tri_state"))
      (node (ref "U$3") (pin "9") (pinfunction "A6_9") (pintype "bidirectional"))
    )
    (net (code "43") (name "Net-(IC3A-A7)") (class "Default")
      (node (ref "IC3") (pin "3") (pinfunction "A7_3") (pintype "input"))
      (node (ref "IC4") (pin "3") (pinfunction "Y4_3") (pintype "tri_state"))
      (node (ref "U$3") (pin "10") (pinfunction "A7_10") (pintype "bidirectional"))
    )
    (net (code "44") (name "Net-(IC3A-A8)") (class "Default")
      (node (ref "IC3") (pin "4") (pinfunction "A8_4") (pintype "input"))
      (node (ref "IC5") (pin "18") (pinfunction "Y1_18") (pintype "tri_state"))
    )
    (net (code "45") (name "Net-(IC3A-A9)") (class "Default")
      (node (ref "IC3") (pin "5") (pinfunction "A9_5") (pintype "input"))
      (node (ref "IC5") (pin "16") (pinfunction "Y2_16") (pintype "tri_state"))
    )
    (net (code "46") (name "Net-(IC3A-A10)") (class "Default")
      (node (ref "IC3") (pin "6") (pinfunction "A10_6") (pintype "input"))
      (node (ref "IC5") (pin "14") (pinfunction "Y3_14") (pintype "tri_state"))
    )
    (net (code "47") (name "Net-(IC3A-A11)") (class "Default")
      (node (ref "IC3") (pin "7") (pinfunction "A11_7") (pintype "input"))
      (node (ref "IC5") (pin "12") (pinfunction "Y4_12") (pintype "tri_state"))
    )
    (net (code "48") (name "Net-(IC3A-A12)") (class "Default")
      (node (ref "IC3") (pin "8") (pinfunction "A12_8") (pintype "input"))
      (node (ref "IC5") (pin "9") (pinfunction "Y1_9") (pintype "tri_state"))
    )
    (net (code "49") (name "Net-(IC3A-A13)") (class "Default")
      (node (ref "IC3") (pin "9") (pinfunction "A13_9") (pintype "input"))
      (node (ref "IC5") (pin "7") (pinfunction "Y2_7") (pintype "tri_state"))
    )
    (net (code "50") (name "Net-(IC3A-A14)") (class "Default")
      (node (ref "IC3") (pin "10") (pinfunction "A14_10") (pintype "input"))
      (node (ref "IC5") (pin "5") (pinfunction "Y3_5") (pintype "tri_state"))
    )
    (net (code "51") (name "Net-(IC3A-~{CE})") (class "Default")
      (node (ref "IC3") (pin "20") (pinfunction "~{CE}_20") (pintype "input"))
      (node (ref "IC6") (pin "6") (pinfunction "O_6") (pintype "output"))
    )
    (net (code "52") (name "Net-(IC3A-~{OE})") (class "Default")
      (node (ref "IC3") (pin "22") (pinfunction "~{OE}_22") (pintype "input"))
      (node (ref "U$1") (pin "P$15") (pinfunction "RD*_P$15") (pintype "bidirectional"))
    )
    (net (code "53") (name "Net-(IC3A-~{WE})") (class "Default")
      (node (ref "IC3") (pin "27") (pinfunction "~{WE}_27") (pintype "input"))
      (node (ref "U$1") (pin "P$13") (pinfunction "WR*_P$13") (pintype "bidirectional"))
    )
    (net (code "54") (name "Net-(IC4A-A1)") (class "Default")
      (node (ref "IC4") (pin "2") (pinfunction "A1_2") (pintype "input"))
      (node (ref "U$1") (pin "P$25") (pinfunction "A0_P$25") (pintype "bidirectional"))
    )
    (net (code "55") (name "Net-(IC4A-A2)") (class "Default")
      (node (ref "IC4") (pin "4") (pinfunction "A2_4") (pintype "input"))
      (node (ref "U$1") (pin "P$27") (pinfunction "A1_P$27") (pintype "bidirectional"))
    )
    (net (code "56") (name "Net-(IC4A-A3)") (class "Default")
      (node (ref "IC4") (pin "6") (pinfunction "A3_6") (pintype "input"))
      (node (ref "U$1") (pin "P$40") (pinfunction "A2_P$40") (pintype "bidirectional"))
    )
    (net (code "57") (name "Net-(IC4A-A4)") (class "Default")
      (node (ref "IC4") (pin "8") (pinfunction "A4_8") (pintype "input"))
      (node (ref "U$1") (pin "P$34") (pinfunction "A3_P$34") (pintype "bidirectional"))
    )
    (net (code "58") (name "Net-(IC4B-A1)") (class "Default")
      (node (ref "IC4") (pin "11") (pinfunction "A1_11") (pintype "input"))
      (node (ref "U$1") (pin "P$31") (pinfunction "A4_P$31") (pintype "bidirectional"))
    )
    (net (code "59") (name "Net-(IC4B-A2)") (class "Default")
      (node (ref "IC4") (pin "13") (pinfunction "A2_13") (pintype "input"))
      (node (ref "U$1") (pin "P$35") (pinfunction "A5_P$35") (pintype "bidirectional"))
    )
    (net (code "60") (name "Net-(IC4B-A3)") (class "Default")
      (node (ref "IC4") (pin "15") (pinfunction "A3_15") (pintype "input"))
      (node (ref "U$1") (pin "P$38") (pinfunction "A6_P$38") (pintype "bidirectional"))
    )
    (net (code "61") (name "Net-(IC4B-A4)") (class "Default")
      (node (ref "IC4") (pin "17") (pinfunction "A4_17") (pintype "input"))
      (node (ref "U$1") (pin "P$36") (pinfunction "A7_P$36") (pintype "bidirectional"))
    )
    (net (code "62") (name "Net-(IC5A-A1)") (class "Default")
      (node (ref "IC5") (pin "2") (pinfunction "A1_2") (pintype "input"))
      (node (ref "U$1") (pin "P$11") (pinfunction "A8_P$11") (pintype "bidirectional"))
    )
    (net (code "63") (name "Net-(IC5A-A2)") (class "Default")
      (node (ref "IC5") (pin "4") (pinfunction "A2_4") (pintype "input"))
      (node (ref "U$1") (pin "P$17") (pinfunction "A9_P$17") (pintype "bidirectional"))
    )
    (net (code "64") (name "Net-(IC5A-A3)") (class "Default")
      (node (ref "IC5") (pin "6") (pinfunction "A3_6") (pintype "input"))
      (node (ref "U$1") (pin "P$4") (pinfunction "A10_P$4") (pintype "bidirectional"))
    )
    (net (code "65") (name "Net-(IC5A-A4)") (class "Default")
      (node (ref "IC5") (pin "8") (pinfunction "A4_8") (pintype "input"))
      (node (ref "U$1") (pin "P$9") (pinfunction "A11_P$9") (pintype "bidirectional"))
    )
    (net (code "66") (name "Net-(IC5B-A1)") (class "Default")
      (node (ref "IC5") (pin "11") (pinfunction "A1_11") (pintype "input"))
      (node (ref "U$1") (pin "P$5") (pinfunction "A12_P$5") (pintype "bidirectional"))
    )
    (net (code "67") (name "Net-(IC5B-A2)") (class "Default")
      (node (ref "IC5") (pin "13") (pinfunction "A2_13") (pintype "input"))
      (node (ref "U$1") (pin "P$6") (pinfunction "A13_P$6") (pintype "bidirectional"))
    )
    (net (code "68") (name "Net-(IC5B-A3)") (class "Default")
      (node (ref "IC5") (pin "15") (pinfunction "A3_15") (pintype "input"))
      (node (ref "U$1") (pin "P$10") (pinfunction "A14_P$10") (pintype "bidirectional"))
    )
    (net (code "69") (name "Net-(IC5B-A4)") (class "Default")
      (node (ref "IC5") (pin "17") (pinfunction "A4_17") (pintype "input"))
      (node (ref "U$1") (pin "P$7") (pinfunction "A15_P$7") (pintype "bidirectional"))
    )
    (net (code "70") (name "Net-(IC5B-Y4)") (class "Default")
      (node (ref "IC5") (pin "3") (pinfunction "Y4_3") (pintype "tri_state"))
      (node (ref "IC6") (pin "4") (pinfunction "I0_4") (pintype "input"))
    )
    (net (code "71") (name "Net-(IC6A-I0)") (class "Default")
      (node (ref "IC6") (pin "1") (pinfunction "I0_1") (pintype "input"))
      (node (ref "U$1") (pin "P$1") (pinfunction "RAS*_P$1") (pintype "bidirectional"))
    )
    (net (code "72") (name "Net-(IC6A-O)") (class "Default")
      (node (ref "IC6") (pin "3") (pinfunction "O_3") (pintype "output"))
      (node (ref "IC6") (pin "5") (pinfunction "I1_5") (pintype "input"))
    )
    (net (code "73") (name "Net-(IC6C-I0)") (class "Default")
      (node (ref "IC6") (pin "9") (pinfunction "I0_9") (pintype "input"))
      (node (ref "R2") (pin "2") (pinfunction "2_2") (pintype "passive"))
      (node (ref "U11") (pin "P4") (pinfunction "READY_P4") (pintype "bidirectional"))
    )
    (net (code "74") (name "Net-(IC6C-I1)") (class "Default")
      (node (ref "IC6") (pin "10") (pinfunction "I1_10") (pintype "input"))
      (node (ref "R6") (pin "2") (pinfunction "2_2") (pintype "passive"))
      (node (ref "U4") (pin "P4") (pinfunction "READY_P4") (pintype "bidirectional"))
    )
    (net (code "75") (name "Net-(IC6C-O)") (class "Default")
      (node (ref "IC6") (pin "12") (pinfunction "I0_12") (pintype "input"))
      (node (ref "IC6") (pin "13") (pinfunction "I1_13") (pintype "input"))
      (node (ref "IC6") (pin "8") (pinfunction "O_8") (pintype "output"))
    )
    (net (code "76") (name "Net-(IC6D-O)") (class "Default")
      (node (ref "IC6") (pin "11") (pinfunction "O_11") (pintype "output"))
      (node (ref "U$1") (pin "P$33") (pinfunction "WAIT*_P$33") (pintype "bidirectional"))
    )
    (net (code "77") (name "Net-(IC7A-I0)") (class "Default")
      (node (ref "IC7") (pin "1") (pinfunction "I0_1") (pintype "input"))
      (node (ref "R9") (pin "1") (pinfunction "1_1") (pintype "passive"))
      (node (ref "U$3") (pin "15") (pinfunction "RESET_OUT_15") (pintype "bidirectional"))
      (node (ref "U2") (pin "P34") (pinfunction "RESET*_P34") (pintype "bidirectional"))
    )
    (net (code "78") (name "Net-(IC8A-A1)") (class "Default")
      (node (ref "IC8") (pin "2") (pinfunction "A1_2") (pintype "input"))
      (node (ref "JOYSTICK1") (pin "2") (pinfunction "2_2") (pintype "passive"))
      (node (ref "RN1") (pin "13") (pinfunction "13_13") (pintype "passive"))
    )
    (net (code "79") (name "Net-(IC8A-A2)") (class "Default")
      (node (ref "IC8") (pin "4") (pinfunction "A2_4") (pintype "input"))
      (node (ref "JOYSTICK1") (pin "3") (pinfunction "3_3") (pintype "passive"))
      (node (ref "RN1") (pin "12") (pinfunction "12_12") (pintype "passive"))
    )
    (net (code "80") (name "Net-(IC8A-A3)") (class "Default")
      (node (ref "IC8") (pin "6") (pinfunction "A3_6") (pintype "input"))
      (node (ref "JOYSTICK1") (pin "4") (pinfunction "4_4") (pintype "passive"))
      (node (ref "RN1") (pin "11") (pinfunction "11_11") (pintype "passive"))
    )
    (net (code "81") (name "Net-(IC8A-A4)") (class "Default")
      (node (ref "IC8") (pin "8") (pinfunction "A4_8") (pintype "input"))
      (node (ref "JOYSTICK1") (pin "5") (pinfunction "5_5") (pintype "passive"))
      (node (ref "RN1") (pin "10") (pinfunction "10_10") (pintype "passive"))
    )
    (net (code "82") (name "Net-(IC8A-G)") (class "Default")
      (node (ref "IC8") (pin "1") (pinfunction "G_1") (pintype "input"))
      (node (ref "IC8") (pin "19") (pinfunction "G_19") (pintype "input"))
      (node (ref "U$3") (pin "18") (pinfunction "JOY1_18") (pintype "bidirectional"))
    )
    (net (code "83") (name "Net-(IC8B-A1)") (class "Default")
      (node (ref "IC8") (pin "11") (pinfunction "A1_11") (pintype "input"))
      (node (ref "JOYSTICK1") (pin "9") (pinfunction "9_9") (pintype "passive"))
      (node (ref "RN1") (pin "9") (pinfunction "9_9") (pintype "passive"))
    )
    (net (code "84") (name "Net-(J4-PadPIN)") (class "Default")
      (node (ref "J4") (pin "PIN") (pinfunction "PIN_PIN") (pintype "bidirectional"))
      (node (ref "J4") (pin "SWITCH") (pinfunction "SWITCH_SWITCH") (pintype "bidirectional"))
      (node (ref "R5") (pin "2") (pinfunction "2_2") (pintype "passive"))
    )
    (net (code "85") (name "Net-(J5-PadPIN)") (class "Default")
      (node (ref "J5") (pin "PIN") (pinfunction "PIN_PIN") (pintype "bidirectional"))
      (node (ref "J5") (pin "SWITCH") (pinfunction "SWITCH_SWITCH") (pintype "bidirectional"))
      (node (ref "R1") (pin "2") (pinfunction "2_2") (pintype "passive"))
    )
    (net (code "86") (name "Net-(R8-E)") (class "Default")
      (node (ref "Q2") (pin "E") (pinfunction "E_E") (pintype "passive"))
      (node (ref "R3") (pin "1") (pinfunction "1_1") (pintype "passive"))
      (node (ref "R8") (pin "3") (pinfunction "E_3") (pintype "passive"))
    )
    (net (code "87") (name "Net-(R8-S)") (class "Default")
      (node (ref "J3") (pin "PIN") (pinfunction "PIN_PIN") (pintype "bidirectional"))
      (node (ref "J3") (pin "SWITCH") (pinfunction "SWITCH_SWITCH") (pintype "bidirectional"))
      (node (ref "R8") (pin "2") (pinfunction "S_2") (pintype "passive"))
    )
    (net (code "88") (name "Net-(REG1-VIN)") (class "Default")
      (node (ref "C5") (pin "+") (pinfunction "+_+") (pintype "passive"))
      (node (ref "REG1") (pin "P$1") (pinfunction "VIN_P$1") (pintype "bidirectional"))
      (node (ref "S1") (pin "1") (pinfunction "O_1") (pintype "passive"))
    )
    (net (code "89") (name "Net-(S1-P)") (class "Default")
      (node (ref "S1") (pin "2") (pinfunction "P_2") (pintype "passive"))
      (node (ref "U$2") (pin "3") (pinfunction "3_3") (pintype "passive"))
    )
    (net (code "90") (name "Net-(U$1-INT*)") (class "Default")
      (node (ref "JP1") (pin "1") (pinfunction "1_1") (pintype "passive"))
      (node (ref "JP2") (pin "1") (pinfunction "1_1") (pintype "passive"))
      (node (ref "U$1") (pin "P$21") (pinfunction "INT*_P$21") (pintype "bidirectional"))
    )
    (net (code "91") (name "Net-(U$1-SYSRES*)") (class "Default")
      (node (ref "U$1") (pin "P$2") (pinfunction "SYSRES*_P$2") (pintype "bidirectional"))
      (node (ref "U$3") (pin "14") (pinfunction "RESET_IN_14") (pintype "bidirectional"))
    )
    (net (code "92") (name "Net-(U$3-CSR)") (class "Default")
      (node (ref "U$3") (pin "21") (pinfunction "CSR_21") (pintype "bidirectional"))
      (node (ref "U2") (pin "P15") (pinfunction "CSR*_P15") (pintype "bidirectional"))
    )
    (net (code "93") (name "Net-(U$3-CSW)") (class "Default")
      (node (ref "U$3") (pin "22") (pinfunction "CSW_22") (pintype "bidirectional"))
      (node (ref "U2") (pin "P14") (pinfunction "CSW*_P14") (pintype "bidirectional"))
    )
    (net (code "94") (name "Net-(U$3-MODE)") (class "Default")
      (node (ref "U$3") (pin "16") (pinfunction "MODE_16") (pintype "bidirectional"))
      (node (ref "U2") (pin "P13") (pinfunction "MODE_P13") (pintype "bidirectional"))
    )
    (net (code "95") (name "Net-(U$3-SND1)") (class "Default")
      (node (ref "U$3") (pin "20") (pinfunction "SND1_20") (pintype "bidirectional"))
      (node (ref "U11") (pin "P5") (pinfunction "WE*_P5") (pintype "bidirectional"))
      (node (ref "U11") (pin "P6") (pinfunction "OE*_P6") (pintype "bidirectional"))
    )
    (net (code "96") (name "Net-(U$3-SND2)") (class "Default")
      (node (ref "U$3") (pin "19") (pinfunction "SND2_19") (pintype "bidirectional"))
      (node (ref "U4") (pin "P5") (pinfunction "WE*_P5") (pintype "bidirectional"))
      (node (ref "U4") (pin "P6") (pinfunction "OE*_P6") (pintype "bidirectional"))
    )
    (net (code "97") (name "Net-(U1-A0)") (class "Default")
      (node (ref "U1") (pin "14") (pinfunction "A0_14") (pintype "bidirectional"))
      (node (ref "U2") (pin "P3") (pinfunction "AD7_P3") (pintype "bidirectional"))
      (node (ref "U3") (pin "14") (pinfunction "A0_14") (pintype "bidirectional"))
    )
    (net (code "98") (name "Net-(U1-A1)") (class "Default")
      (node (ref "U1") (pin "13") (pinfunction "A1_13") (pintype "bidirectional"))
      (node (ref "U2") (pin "P4") (pinfunction "AD6_P4") (pintype "bidirectional"))
      (node (ref "U3") (pin "13") (pinfunction "A1_13") (pintype "bidirectional"))
    )
    (net (code "99") (name "Net-(U1-A2)") (class "Default")
      (node (ref "U1") (pin "12") (pinfunction "A2_12") (pintype "bidirectional"))
      (node (ref "U2") (pin "P5") (pinfunction "AD5_P5") (pintype "bidirectional"))
      (node (ref "U3") (pin "12") (pinfunction "A2_12") (pintype "bidirectional"))
    )
    (net (code "100") (name "Net-(U1-A3)") (class "Default")
      (node (ref "U1") (pin "11") (pinfunction "A3_11") (pintype "bidirectional"))
      (node (ref "U2") (pin "P6") (pinfunction "AD4_P6") (pintype "bidirectional"))
      (node (ref "U3") (pin "11") (pinfunction "A3_11") (pintype "bidirectional"))
    )
    (net (code "101") (name "Net-(U1-A4)") (class "Default")
      (node (ref "U1") (pin "8") (pinfunction "A4_8") (pintype "bidirectional"))
      (node (ref "U2") (pin "P7") (pinfunction "AD3_P7") (pintype "bidirectional"))
      (node (ref "U3") (pin "8") (pinfunction "A4_8") (pintype "bidirectional"))
    )
    (net (code "102") (name "Net-(U1-A5)") (class "Default")
      (node (ref "U1") (pin "7") (pinfunction "A5_7") (pintype "bidirectional"))
      (node (ref "U2") (pin "P8") (pinfunction "AD2_P8") (pintype "bidirectional"))
      (node (ref "U3") (pin "7") (pinfunction "A5_7") (pintype "bidirectional"))
    )
    (net (code "103") (name "Net-(U1-A6)") (class "Default")
      (node (ref "U1") (pin "6") (pinfunction "A6_6") (pintype "bidirectional"))
      (node (ref "U2") (pin "P9") (pinfunction "AD1_P9") (pintype "bidirectional"))
      (node (ref "U3") (pin "6") (pinfunction "A6_6") (pintype "bidirectional"))
    )
    (net (code "104") (name "Net-(U1-A7)") (class "Default")
      (node (ref "U1") (pin "10") (pinfunction "A7_10") (pintype "bidirectional"))
      (node (ref "U2") (pin "P10") (pinfunction "AD0_P10") (pintype "bidirectional"))
      (node (ref "U3") (pin "10") (pinfunction "A7_10") (pintype "bidirectional"))
    )
    (net (code "105") (name "Net-(U1-CAS*)") (class "Default")
      (node (ref "U1") (pin "16") (pinfunction "CAS*_16") (pintype "bidirectional"))
      (node (ref "U2") (pin "P2") (pinfunction "CAS*_P2") (pintype "bidirectional"))
      (node (ref "U3") (pin "16") (pinfunction "CAS*_16") (pintype "bidirectional"))
    )
    (net (code "106") (name "Net-(U1-DQ1)") (class "Default")
      (node (ref "U1") (pin "2") (pinfunction "DQ1_2") (pintype "bidirectional"))
      (node (ref "U2") (pin "P32") (pinfunction "RD0_P32") (pintype "bidirectional"))
    )
    (net (code "107") (name "Net-(U1-DQ2)") (class "Default")
      (node (ref "U1") (pin "3") (pinfunction "DQ2_3") (pintype "bidirectional"))
      (node (ref "U2") (pin "P31") (pinfunction "RD1_P31") (pintype "bidirectional"))
    )
    (net (code "108") (name "Net-(U1-DQ3)") (class "Default")
      (node (ref "U1") (pin "15") (pinfunction "DQ3_15") (pintype "bidirectional"))
      (node (ref "U2") (pin "P30") (pinfunction "RD2_P30") (pintype "bidirectional"))
    )
    (net (code "109") (name "Net-(U1-DQ4)") (class "Default")
      (node (ref "U1") (pin "17") (pinfunction "DQ4_17") (pintype "bidirectional"))
      (node (ref "U2") (pin "P29") (pinfunction "RD3_P29") (pintype "bidirectional"))
    )
    (net (code "110") (name "Net-(U1-RAS*)") (class "Default")
      (node (ref "U1") (pin "5") (pinfunction "RAS*_5") (pintype "bidirectional"))
      (node (ref "U2") (pin "P1") (pinfunction "RAS*_P1") (pintype "bidirectional"))
      (node (ref "U3") (pin "5") (pinfunction "RAS*_5") (pintype "bidirectional"))
    )
    (net (code "111") (name "Net-(U1-W*)") (class "Default")
      (node (ref "U1") (pin "4") (pinfunction "W*_4") (pintype "bidirectional"))
      (node (ref "U2") (pin "P11") (pinfunction "R/W*_P11") (pintype "bidirectional"))
      (node (ref "U3") (pin "4") (pinfunction "W*_4") (pintype "bidirectional"))
    )
    (net (code "112") (name "Net-(U2-COMVID)") (class "Default")
      (node (ref "Q2") (pin "B") (pinfunction "B_B") (pintype "passive"))
      (node (ref "R4") (pin "1") (pinfunction "1_1") (pintype "passive"))
      (node (ref "U2") (pin "P36") (pinfunction "COMVID_P36") (pintype "bidirectional"))
    )
    (net (code "113") (name "Net-(U2-EXTVDP)") (class "Default")
      (node (ref "J2") (pin "PIN") (pinfunction "PIN_PIN") (pintype "bidirectional"))
      (node (ref "J2") (pin "SWITCH") (pinfunction "SWITCH_SWITCH") (pintype "bidirectional"))
      (node (ref "U2") (pin "P35") (pinfunction "EXTVDP_P35") (pintype "bidirectional"))
    )
    (net (code "114") (name "Net-(U2-INT*)") (class "Default")
      (node (ref "JP1") (pin "2") (pinfunction "2_2") (pintype "passive"))
      (node (ref "U2") (pin "P16") (pinfunction "INT*_P16") (pintype "bidirectional"))
    )
    (net (code "115") (name "Net-(U2-RD4)") (class "Default")
      (node (ref "U2") (pin "P28") (pinfunction "RD4_P28") (pintype "bidirectional"))
      (node (ref "U3") (pin "2") (pinfunction "DQ1_2") (pintype "bidirectional"))
    )
    (net (code "116") (name "Net-(U2-RD5)") (class "Default")
      (node (ref "U2") (pin "P27") (pinfunction "RD5_P27") (pintype "bidirectional"))
      (node (ref "U3") (pin "3") (pinfunction "DQ2_3") (pintype "bidirectional"))
    )
    (net (code "117") (name "Net-(U2-RD6)") (class "Default")
      (node (ref "U2") (pin "P26") (pinfunction "RD6_P26") (pintype "bidirectional"))
      (node (ref "U3") (pin "15") (pinfunction "DQ3_15") (pintype "bidirectional"))
    )
    (net (code "118") (name "Net-(U2-RD7)") (class "Default")
      (node (ref "U2") (pin "P25") (pinfunction "RD7_P25") (pintype "bidirectional"))
      (node (ref "U3") (pin "17") (pinfunction "DQ4_17") (pintype "bidirectional"))
    )
    (net (code "119") (name "Net-(U2-XTAL1)") (class "Default")
      (node (ref "C9") (pin "2") (pinfunction "2_2") (pintype "passive"))
      (node (ref "Q1") (pin "1") (pinfunction "1_1") (pintype "passive"))
      (node (ref "U2") (pin "P40") (pinfunction "XTAL1_P40") (pintype "bidirectional"))
    )
    (net (code "120") (name "Net-(U4-SNDOUT)") (class "Default")
      (node (ref "C1") (pin "+") (pinfunction "+_+") (pintype "passive"))
      (node (ref "U4") (pin "P7") (pinfunction "SNDOUT_P7") (pintype "bidirectional"))
    )
    (net (code "121") (name "Net-(U11-SNDOUT)") (class "Default")
      (node (ref "C27") (pin "+") (pinfunction "+_+") (pintype "passive"))
      (node (ref "U11") (pin "P7") (pinfunction "SNDOUT_P7") (pintype "bidirectional"))
    )
    (net (code "122") (name "VCC") (class "Default")
      (node (ref "C10") (pin "1") (pinfunction "1_1") (pintype "passive"))
      (node (ref "C11") (pin "1") (pinfunction "1_1") (pintype "passive"))
      (node (ref "C12") (pin "1") (pinfunction "1_1") (pintype "passive"))
      (node (ref "C13") (pin "1") (pinfunction "1_1") (pintype "passive"))
      (node (ref "C14") (pin "1") (pinfunction "1_1") (pintype "passive"))
      (node (ref "C15") (pin "1") (pinfunction "1_1") (pintype "passive"))
      (node (ref "C16") (pin "1") (pinfunction "1_1") (pintype "passive"))
      (node (ref "C17") (pin "1") (pinfunction "1_1") (pintype "passive"))
      (node (ref "C18") (pin "1") (pinfunction "1_1") (pintype "passive"))
      (node (ref "C20") (pin "1") (pinfunction "1_1") (pintype "passive"))
      (node (ref "C21") (pin "1") (pinfunction "1_1") (pintype "passive"))
      (node (ref "C4") (pin "+") (pinfunction "+_+") (pintype "passive"))
      (node (ref "C6") (pin "1") (pinfunction "1_1") (pintype "passive"))
      (node (ref "C7") (pin "1") (pinfunction "1_1") (pintype "passive"))
      (node (ref "C8") (pin "1") (pinfunction "1_1") (pintype "passive"))
      (node (ref "IC1") (pin "20") (pinfunction "VCC_20") (pintype "power_in"))
      (node (ref "IC2") (pin "12") (pinfunction "CS0_12") (pintype "input"))
      (node (ref "IC2") (pin "13") (pinfunction "CS1_13") (pintype "input"))
      (node (ref "IC2") (pin "39") (pinfunction "RI~{}_39") (pintype "input"))
      (node (ref "IC2") (pin "40") (pinfunction "VCC_40") (pintype "power_in"))
      (node (ref "IC3") (pin "28") (pinfunction "VCC_28") (pintype "power_in"))
      (node (ref "IC4") (pin "20") (pinfunction "VCC_20") (pintype "power_in"))
      (node (ref "IC5") (pin "20") (pinfunction "VCC_20") (pintype "power_in"))
      (node (ref "IC6") (pin "14") (pinfunction "VCC_14") (pintype "power_in"))
      (node (ref "IC6") (pin "2") (pinfunction "I1_2") (pintype "input"))
      (node (ref "IC7") (pin "14") (pinfunction "VCC_14") (pintype "power_in"))
      (node (ref "IC7") (pin "2") (pinfunction "I1_2") (pintype "input"))
      (node (ref "IC8") (pin "20") (pinfunction "VCC_20") (pintype "power_in"))
      (node (ref "J1") (pin "3") (pinfunction "3_3") (pintype "passive"))
      (node (ref "Q2") (pin "C") (pinfunction "C_C") (pintype "passive"))
      (node (ref "R2") (pin "1") (pinfunction "1_1") (pintype "passive"))
      (node (ref "R6") (pin "1") (pinfunction "1_1") (pintype "passive"))
      (node (ref "R7") (pin "1") (pinfunction "1_1") (pintype "passive"))
      (node (ref "R9") (pin "2") (pinfunction "2_2") (pintype "passive"))
      (node (ref "REG1") (pin "P$3") (pinfunction "VOUT_P$3") (pintype "bidirectional"))
      (node (ref "RN1") (pin "1") (pinfunction "1_1") (pintype "passive"))
      (node (ref "U$3") (pin "24") (pinfunction "VCC_24") (pintype "bidirectional"))
      (node (ref "U1") (pin "9") (pinfunction "VDD_9") (pintype "bidirectional"))
      (node (ref "U11") (pin "P16") (pinfunction "VCC_P16") (pintype "bidirectional"))
      (node (ref "U2") (pin "P33") (pinfunction "VDD_P33") (pintype "bidirectional"))
      (node (ref "U3") (pin "9") (pinfunction "VDD_9") (pintype "bidirectional"))
      (node (ref "U4") (pin "P16") (pinfunction "VCC_P16") (pintype "bidirectional"))
    )
    (net (code "123") (name "unconnected-(IC2A-DDIS~{}-Pad23)") (class "Default")
      (node (ref "IC2") (pin "23") (pinfunction "DDIS~{}_23") (pintype "output"))
    )
    (net (code "124") (name "unconnected-(IC2A-DTR~{}-Pad33)") (class "Default")
      (node (ref "IC2") (pin "33") (pinfunction "DTR~{}_33") (pintype "output"))
    )
    (net (code "125") (name "unconnected-(IC2A-RXRDY~{}-Pad29)") (class "Default")
      (node (ref "IC2") (pin "29") (pinfunction "RXRDY~{}_29") (pintype "output"))
    )
    (net (code "126") (name "unconnected-(IC2A-TXRDY~{}-Pad24)") (class "Default")
      (node (ref "IC2") (pin "24") (pinfunction "TXRDY~{}_24") (pintype "output"))
    )
    (net (code "127") (name "unconnected-(IC2A-XTAL2-Pad17)") (class "Default")
      (node (ref "IC2") (pin "17") (pinfunction "XTAL2_17") (pintype "input"))
    )
    (net (code "128") (name "unconnected-(IC7B-O-Pad6)") (class "Default")
      (node (ref "IC7") (pin "6") (pinfunction "O_6") (pintype "output"))
    )
    (net (code "129") (name "unconnected-(IC7C-O-Pad8)") (class "Default")
      (node (ref "IC7") (pin "8") (pinfunction "O_8") (pintype "output"))
    )
    (net (code "130") (name "unconnected-(IC7D-O-Pad11)") (class "Default")
      (node (ref "IC7") (pin "11") (pinfunction "O_11") (pintype "output"))
    )
    (net (code "131") (name "unconnected-(JOYSTICK1-Pad1)") (class "Default")
      (node (ref "JOYSTICK1") (pin "1") (pinfunction "1_1") (pintype "passive"))
    )
    (net (code "132") (name "unconnected-(JOYSTICK1-Pad6)") (class "Default")
      (node (ref "JOYSTICK1") (pin "6") (pinfunction "6_6") (pintype "passive"))
    )
    (net (code "133") (name "unconnected-(JOYSTICK1-Pad8)") (class "Default")
      (node (ref "JOYSTICK1") (pin "8") (pinfunction "8_8") (pintype "passive"))
    )
    (net (code "134") (name "unconnected-(JOYSTICK2-Pad1)") (class "Default")
      (node (ref "JOYSTICK2") (pin "1") (pinfunction "1_1") (pintype "passive"))
    )
    (net (code "135") (name "unconnected-(JOYSTICK2-Pad6)") (class "Default")
      (node (ref "JOYSTICK2") (pin "6") (pinfunction "6_6") (pintype "passive"))
    )
    (net (code "136") (name "unconnected-(JOYSTICK2-Pad8)") (class "Default")
      (node (ref "JOYSTICK2") (pin "8") (pinfunction "8_8") (pintype "passive"))
    )
    (net (code "137") (name "unconnected-(R8-A-Pad1)") (class "Default")
      (node (ref "R8") (pin "1") (pinfunction "A_1") (pintype "passive"))
    )
    (net (code "138") (name "unconnected-(RN1-Pad2)") (class "Default")
      (node (ref "RN1") (pin "2") (pinfunction "2_2") (pintype "passive"))
    )
    (net (code "139") (name "unconnected-(S1-S-Pad3)") (class "Default")
      (node (ref "S1") (pin "3") (pinfunction "S_3") (pintype "passive"))
    )
    (net (code "140") (name "unconnected-(U$1-CAS*-PadP$3)") (class "Default")
      (node (ref "U$1") (pin "P$3") (pinfunction "CAS*_P$3") (pintype "bidirectional"))
    )
    (net (code "141") (name "unconnected-(U$1-GND3-PadP$37)") (class "Default")
      (node (ref "U$1") (pin "P$37") (pinfunction "GND3_P$37") (pintype "bidirectional"))
    )
    (net (code "142") (name "unconnected-(U$1-INTAK*-PadP$14)") (class "Default")
      (node (ref "U$1") (pin "P$14") (pinfunction "INTAK*_P$14") (pintype "bidirectional"))
    )
    (net (code "143") (name "unconnected-(U$1-MUX-PadP$16)") (class "Default")
      (node (ref "U$1") (pin "P$16") (pinfunction "MUX_P$16") (pintype "bidirectional"))
    )
    (net (code "144") (name "unconnected-(U$1-NC-PadP$39)") (class "Default")
      (node (ref "U$1") (pin "P$39") (pinfunction "NC_P$39") (pintype "bidirectional"))
    )
    (net (code "145") (name "unconnected-(U$1-TEST*-PadP$23)") (class "Default")
      (node (ref "U$1") (pin "P$23") (pinfunction "TEST*_P$23") (pintype "bidirectional"))
    )
    (net (code "146") (name "unconnected-(U$3-NC-Pad1)") (class "Default")
      (node (ref "U$3") (pin "1") (pinfunction "NC_1") (pintype "bidirectional"))
    )
    (net (code "147") (name "unconnected-(U$3-NC2-Pad4)") (class "Default")
      (node (ref "U$3") (pin "4") (pinfunction "NC2_4") (pintype "bidirectional"))
    )
    (net (code "148") (name "unconnected-(U2-NC-PadP37)") (class "Default")
      (node (ref "U2") (pin "P37") (pinfunction "NC_P37") (pintype "bidirectional"))
    )
    (net (code "149") (name "unconnected-(U4-NC-PadP9)") (class "Default")
      (node (ref "U4") (pin "P9") (pinfunction "NC_P9") (pintype "bidirectional"))
    )
    (net (code "150") (name "unconnected-(U11-NC-PadP9)") (class "Default")
      (node (ref "U11") (pin "P9") (pinfunction "NC_P9") (pintype "bidirectional"))
    )
  )
)
